# single_LED.net
KiCad netlist of a schematic drawn in EAGLE
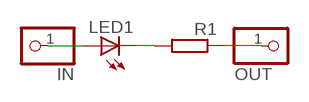
[diagram p0: schematic, sheet 1]

(export (version "E")
  (design (tool "Eeschema 10.0.6"))
  (components
    (comp (ref "IN")
      (value "PINHD-1X1CB")
      (footprint "eagle-import:1X01-CLEANBIG")
      (libsource (lib "eagle-import") (part "PINHD-1X1CB"))
    )
    (comp (ref "LED1")
      (value "LED-0805")
      (footprint "eagle-import:LED-805")
      (libsource (lib "eagle-import") (part "LED-0805"))
    )
    (comp (ref "OUT")
      (value "PINHD-1X1CB")
      (footprint "eagle-import:1X01-CLEANBIG")
      (libsource (lib "eagle-import") (part "PINHD-1X1CB"))
    )
    (comp (ref "R1")
      (value "RESISTORR805-0805")
      (footprint "eagle-import:R805")
      (libsource (lib "eagle-import") (part "RESISTOR-0805R805"))
    )
  )
  (nets
    (net (code "1") (name "Net-(IN-Pad1)") (class "Default")
      (node (ref "IN") (pin "1") (pinfunction "1_1") (pintype "passive"))
      (node (ref "LED1") (pin "A") (pinfunction "A_A") (pintype "passive"))
    )
    (net (code "2") (name "Net-(LED1-PadC)") (class "Default")
      (node (ref "LED1") (pin "C") (pinfunction "C_C") (pintype "passive"))
      (node (ref "R1") (pin "2") (pinfunction "2_2") (pintype "passive"))
    )
    (net (code "3") (name "Net-(OUT-Pad1)") (class "Default")
      (node (ref "OUT") (pin "1") (pinfunction "1_1") (pintype "passive"))
      (node (ref "R1") (pin "1") (pinfunction "1_1") (pintype "passive"))
    )
  )
)
